# 1_27mm.net
KiCad netlist of a schematic drawn in EasyEDA Pro
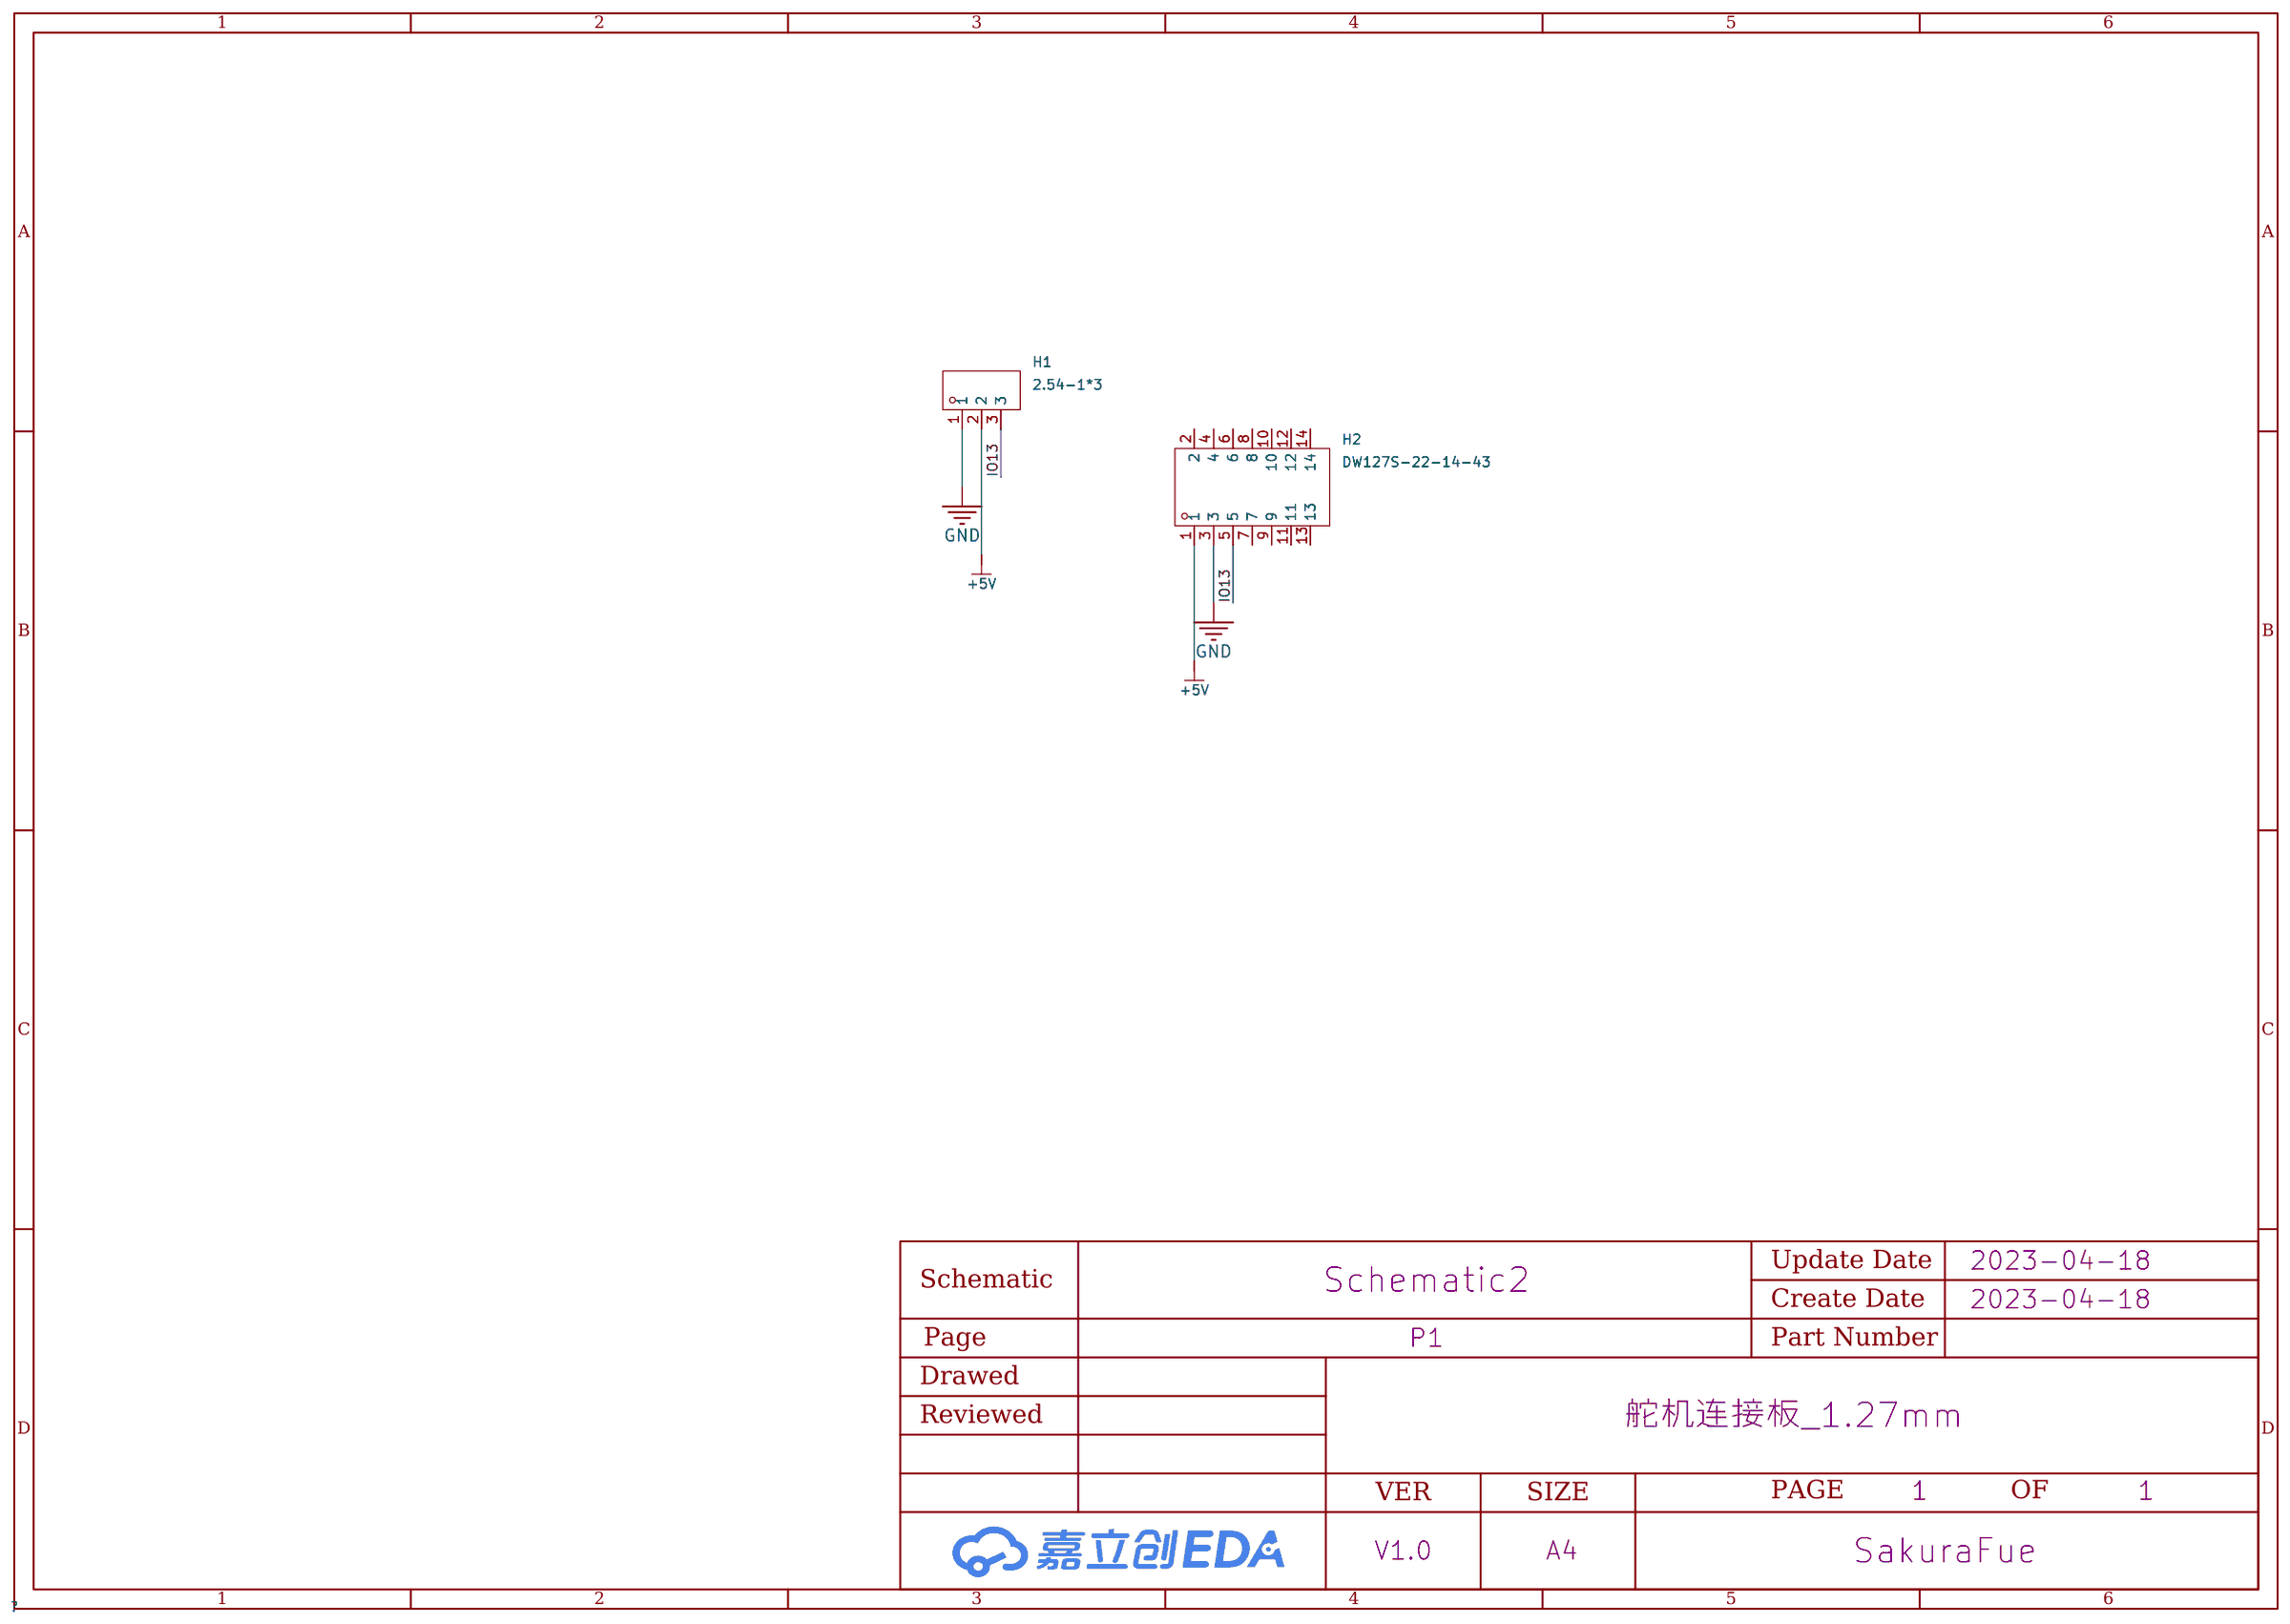
[diagram p0: schematic sheet]

(export (version "E")
  (design (tool "Eeschema 10.0.6"))
  (components
    (comp (ref "H1")
      (value "2.54-1*3")
      (footprint "easyedapro:HDR-TH_3P-P2.54-V-M-1")
      (description "排针 2.54mm 1x3P 镀金3u")
      (fields (field (name "Manufacturer") "ZHOURI(洲日)"))
      (libsource (lib "easyedapro") (part "2.54-1*3"))
    )
    (comp (ref "H2")
      (value "DW127S-22-14-43")
      (footprint "easyedapro:HDR-SMD_14P-P1.27-V-F-R2-C7-LS4.8")
      (description "排数:双排;总孔位数:14;间距:1.27mm;插孔结构:2x7P;安装类型:立贴;")
      (fields (field (name "Manufacturer") "DEALON(德艺隆)"))
      (libsource (lib "easyedapro") (part "DW127S-22-14-43"))
    )
  )
  (nets
    (net (code "1") (name "+5V") (class "Default")
      (node (ref "H1") (pin "2") (pinfunction "2_2") (pintype "input"))
      (node (ref "H2") (pin "1") (pinfunction "1_1") (pintype "input"))
    )
    (net (code "2") (name "/IO13") (class "Default")
      (node (ref "H1") (pin "3") (pinfunction "3_3") (pintype "input"))
      (node (ref "H2") (pin "5") (pinfunction "5_5") (pintype "input"))
    )
    (net (code "3") (name "GND") (class "Default")
      (node (ref "H1") (pin "1") (pinfunction "1_1") (pintype "input"))
      (node (ref "H2") (pin "3") (pinfunction "3_3") (pintype "input"))
    )
    (net (code "4") (name "unconnected-(H2-Pad2)") (class "Default")
      (node (ref "H2") (pin "2") (pinfunction "2_2") (pintype "input"))
    )
    (net (code "5") (name "unconnected-(H2-Pad4)") (class "Default")
      (node (ref "H2") (pin "4") (pinfunction "4_4") (pintype "input"))
    )
    (net (code "6") (name "unconnected-(H2-Pad6)") (class "Default")
      (node (ref "H2") (pin "6") (pinfunction "6_6") (pintype "input"))
    )
    (net (code "7") (name "unconnected-(H2-Pad7)") (class "Default")
      (node (ref "H2") (pin "7") (pinfunction "7_7") (pintype "input"))
    )
    (net (code "8") (name "unconnected-(H2-Pad8)") (class "Default")
      (node (ref "H2") (pin "8") (pinfunction "8_8") (pintype "input"))
    )
    (net (code "9") (name "unconnected-(H2-Pad9)") (class "Default")
      (node (ref "H2") (pin "9") (pinfunction "9_9") (pintype "input"))
    )
    (net (code "10") (name "unconnected-(H2-Pad10)") (class "Default")
      (node (ref "H2") (pin "10") (pinfunction "10_10") (pintype "input"))
    )
    (net (code "11") (name "unconnected-(H2-Pad11)") (class "Default")
      (node (ref "H2") (pin "11") (pinfunction "11_11") (pintype "input"))
    )
    (net (code "12") (name "unconnected-(H2-Pad12)") (class "Default")
      (node (ref "H2") (pin "12") (pinfunction "12_12") (pintype "input"))
    )
    (net (code "13") (name "unconnected-(H2-Pad13)") (class "Default")
      (node (ref "H2") (pin "13") (pinfunction "13_13") (pintype "input"))
    )
    (net (code "14") (name "unconnected-(H2-Pad14)") (class "Default")
      (node (ref "H2") (pin "14") (pinfunction "14_14") (pintype "input"))
    )
  )
)
